# E-Book_Reader_Schematic.net
KiCad netlist of a schematic drawn in EAGLE
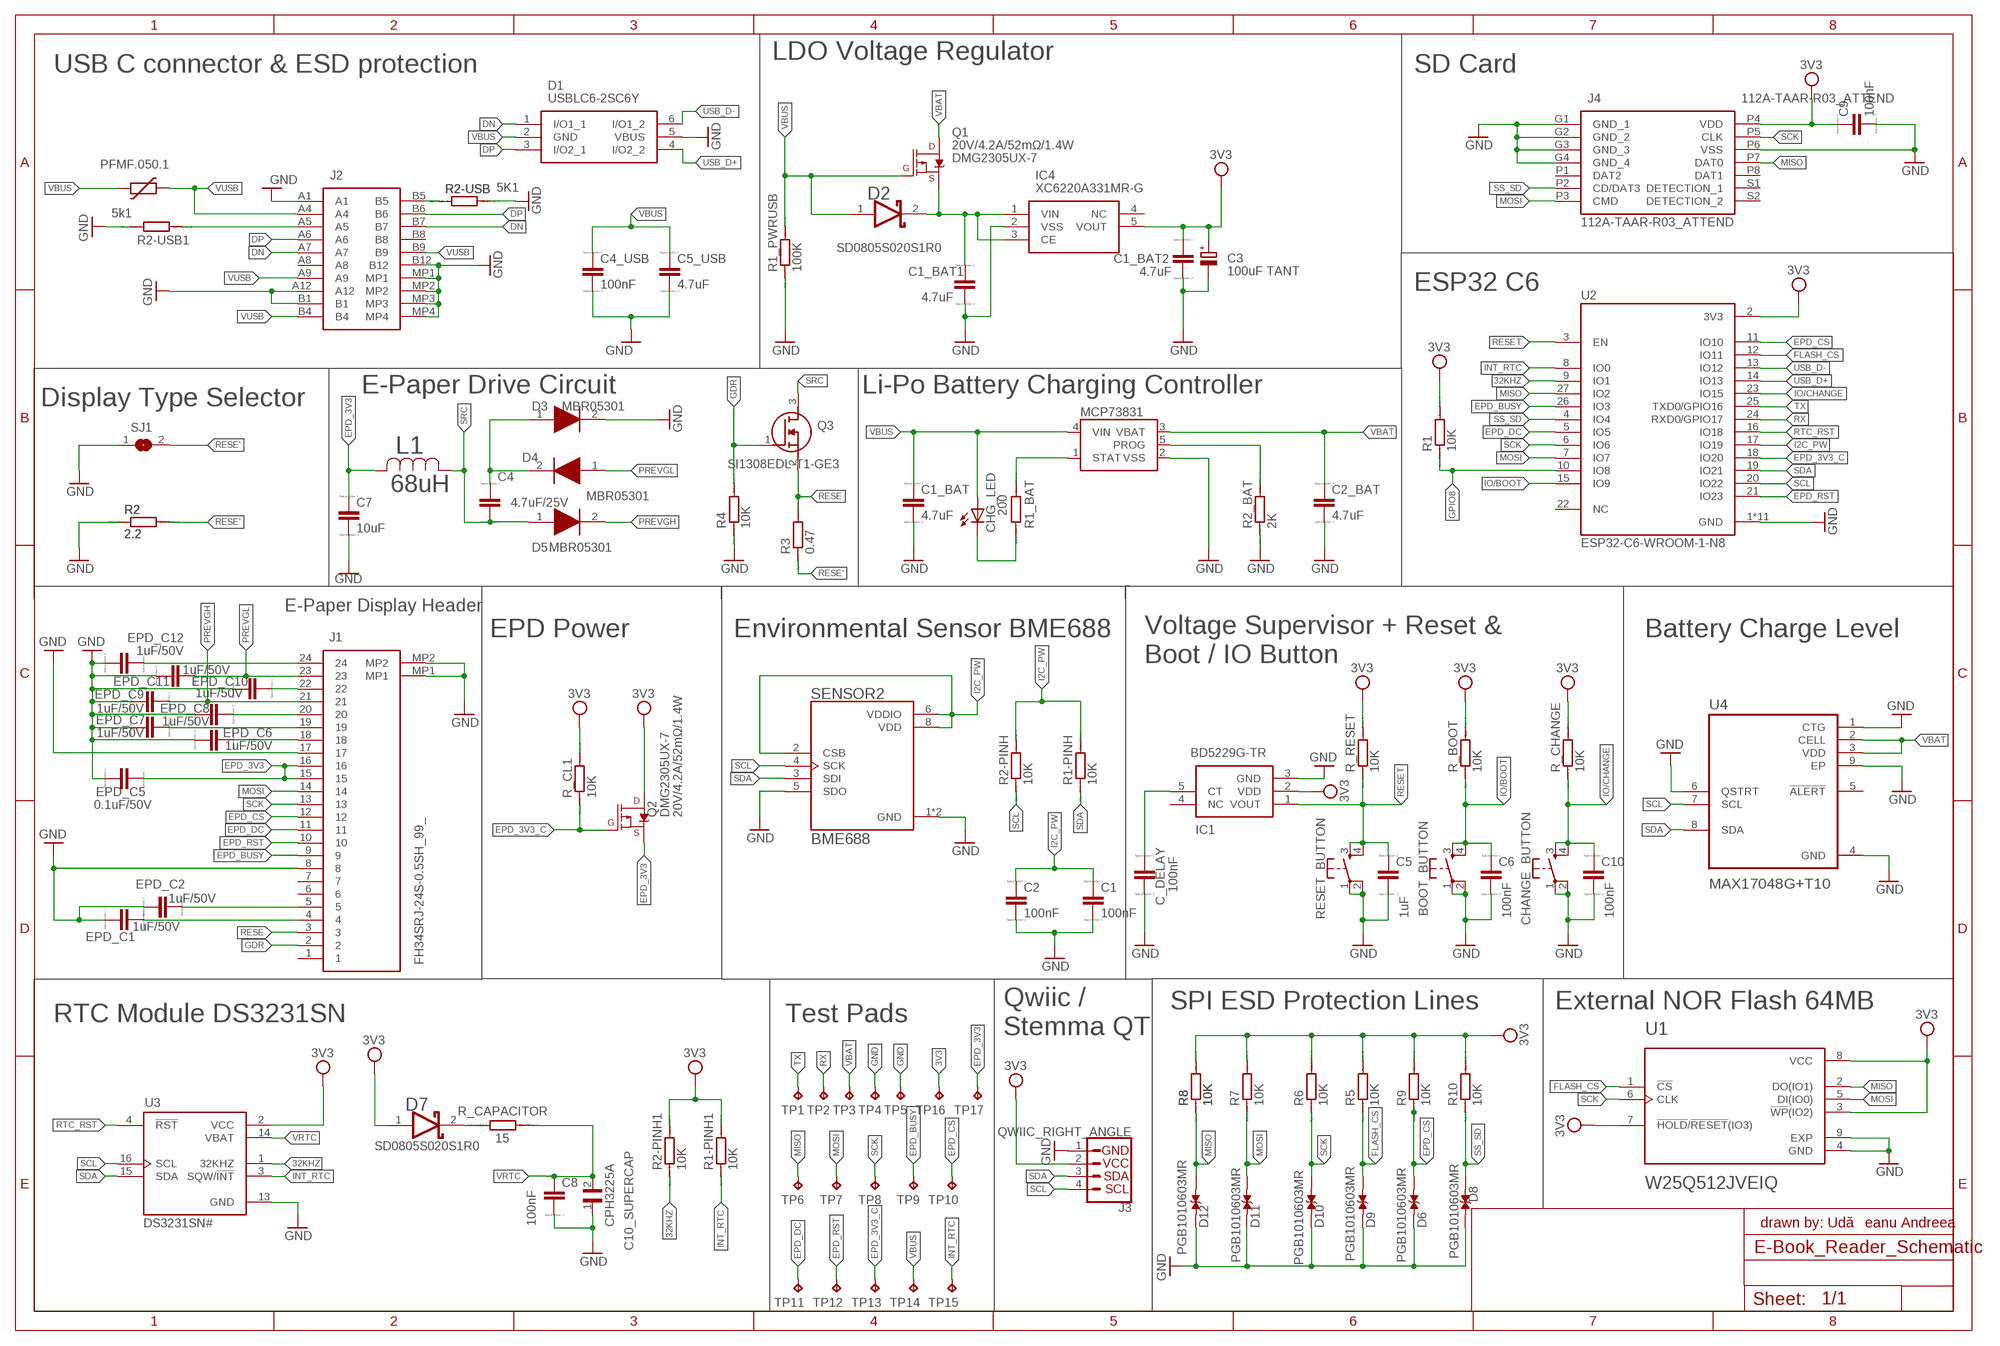
[diagram p0: schematic, sheet 1]

(export (version "E")
  (design (tool "Eeschema 10.0.6"))
  (components
    (comp (ref "BOOT_BUTTON")
      (value "BUTTON_CUSYOMV1")
      (footprint "eagle-import:MYBUTTON")
      (libsource (lib "eagle-import") (part "BUTTON_CUSYOMV1"))
    )
    (comp (ref "C1")
      (value "100nF")
      (footprint "eagle-import:EAGLE-LTSPICE_C0402")
      (libsource (lib "eagle-import") (part "EAGLE-LTSPICE_CC0402"))
    )
    (comp (ref "C1_BAT")
      (value "4.7uF")
      (footprint "eagle-import:EAGLE-LTSPICE_C0402")
      (libsource (lib "eagle-import") (part "EAGLE-LTSPICE_CC0402"))
    )
    (comp (ref "C1_BAT1")
      (value "4.7uF")
      (footprint "eagle-import:EAGLE-LTSPICE_C0402")
      (libsource (lib "eagle-import") (part "EAGLE-LTSPICE_CC0402"))
    )
    (comp (ref "C1_BAT2")
      (value "4.7uF")
      (footprint "eagle-import:EAGLE-LTSPICE_C0402")
      (libsource (lib "eagle-import") (part "EAGLE-LTSPICE_CC0402"))
    )
    (comp (ref "C2")
      (value "100nF")
      (footprint "eagle-import:EAGLE-LTSPICE_C0402")
      (libsource (lib "eagle-import") (part "EAGLE-LTSPICE_CC0402"))
    )
    (comp (ref "C2_BAT")
      (value "4.7uF")
      (footprint "eagle-import:EAGLE-LTSPICE_C0402")
      (libsource (lib "eagle-import") (part "EAGLE-LTSPICE_CC0402"))
    )
    (comp (ref "C3")
      (value "100uF TANT")
      (footprint "eagle-import:RCL_CT3528")
      (libsource (lib "eagle-import") (part "RCL_CPOL-EUCT3528"))
    )
    (comp (ref "C4")
      (value "4.7uF/25V")
      (footprint "eagle-import:EAGLE-LTSPICE_C0402")
      (libsource (lib "eagle-import") (part "EAGLE-LTSPICE_CC0402"))
    )
    (comp (ref "C4_USB")
      (value "100nF")
      (footprint "eagle-import:ESP32_WROVER_EAGLE-LTSPICE_C0402")
      (libsource (lib "eagle-import") (part "ESP32_WROVER_EAGLE-LTSPICE_CC0402"))
    )
    (comp (ref "C5")
      (value "1uF")
      (footprint "eagle-import:EAGLE-LTSPICE_C0402")
      (libsource (lib "eagle-import") (part "EAGLE-LTSPICE_CC0402"))
    )
    (comp (ref "C5_USB")
      (value "4.7uF")
      (footprint "eagle-import:ESP32_WROVER_EAGLE-LTSPICE_C0402")
      (libsource (lib "eagle-import") (part "ESP32_WROVER_EAGLE-LTSPICE_CC0402"))
    )
    (comp (ref "C6")
      (value "100nF")
      (footprint "eagle-import:EAGLE-LTSPICE_C0402")
      (libsource (lib "eagle-import") (part "EAGLE-LTSPICE_CC0402"))
    )
    (comp (ref "C7")
      (value "10uF")
      (footprint "eagle-import:EAGLE-LTSPICE_C0402")
      (libsource (lib "eagle-import") (part "EAGLE-LTSPICE_CC0402"))
    )
    (comp (ref "C8")
      (value "100nF")
      (footprint "eagle-import:EAGLE-LTSPICE_C0402")
      (libsource (lib "eagle-import") (part "EAGLE-LTSPICE_CC0402"))
    )
    (comp (ref "C9")
      (value "100nF")
      (footprint "eagle-import:ESP32_WROVER_EAGLE-LTSPICE_C0402")
      (libsource (lib "eagle-import") (part "ESP32_WROVER_EAGLE-LTSPICE_CC0402"))
    )
    (comp (ref "C10")
      (value "100nF")
      (footprint "eagle-import:EAGLE-LTSPICE_C0402")
      (libsource (lib "eagle-import") (part "EAGLE-LTSPICE_CC0402"))
    )
    (comp (ref "C10_SUPERCAP")
      (value "CPH3225A")
      (footprint "eagle-import:CAPCP3225X100N")
      (fields (field (name "MF") "Seiko Instruments"))
      (libsource (lib "eagle-import") (part "CPH3225A"))
    )
    (comp (ref "CHANGE_BUTTON")
      (value "BUTTON_CUSYOMV1")
      (footprint "eagle-import:MYBUTTON")
      (libsource (lib "eagle-import") (part "BUTTON_CUSYOMV1"))
    )
    (comp (ref "CHG_LED")
      (value "ADAFRUIT_LEDCHIP-LED0603")
      (footprint "eagle-import:ADAFRUIT_CHIP-LED0603")
      (libsource (lib "eagle-import") (part "ADAFRUIT_LEDCHIP-LED0603"))
    )
    (comp (ref "C_DELAY")
      (value "100nF")
      (footprint "eagle-import:EAGLE-LTSPICE_C0402")
      (libsource (lib "eagle-import") (part "EAGLE-LTSPICE_CC0402"))
    )
    (comp (ref "D1")
      (value "USBLC6-2SC6Y")
      (footprint "eagle-import:SOT95P280X145-6N")
      (fields (field (name "MF") "STMicroelectronics"))
      (libsource (lib "eagle-import") (part "USBLC6-2SC6Y"))
    )
    (comp (ref "D2")
      (value "SD0805S020S1R0")
      (footprint "eagle-import:ESP32_WROVER_AVX---SD0805S020S1R0_AVX_SD0805S020S1R0_0")
      (libsource (lib "eagle-import") (part "ESP32_WROVER_AVX---SD0805S020S1R0_AVX_SD0805S020S1R0_0_0"))
    )
    (comp (ref "D3")
      (value "MBR05301")
      (footprint "eagle-import:SOD3716X135N")
      (libsource (lib "eagle-import") (part "MBR05301"))
    )
    (comp (ref "D4")
      (value "MBR05301")
      (footprint "eagle-import:SOD3716X135N")
      (libsource (lib "eagle-import") (part "MBR05301"))
    )
    (comp (ref "D5")
      (value "MBR05301")
      (footprint "eagle-import:SOD3716X135N")
      (libsource (lib "eagle-import") (part "MBR05301"))
    )
    (comp (ref "D6")
      (value "PGB1010603MR")
      (footprint "eagle-import:DIOC1608X36N")
      (fields (field (name "MF") "Littelfuse Inc."))
      (libsource (lib "eagle-import") (part "PGB1010603MR"))
    )
    (comp (ref "D7")
      (value "SD0805S020S1R0")
      (footprint "eagle-import:ESP32_WROVER_AVX---SD0805S020S1R0_AVX_SD0805S020S1R0_0")
      (libsource (lib "eagle-import") (part "ESP32_WROVER_AVX---SD0805S020S1R0_AVX_SD0805S020S1R0_0_0"))
    )
    (comp (ref "D8")
      (value "PGB1010603MR")
      (footprint "eagle-import:DIOC1608X36N")
      (fields (field (name "MF") "Littelfuse Inc."))
      (libsource (lib "eagle-import") (part "PGB1010603MR"))
    )
    (comp (ref "D9")
      (value "PGB1010603MR")
      (footprint "eagle-import:DIOC1608X36N")
      (fields (field (name "MF") "Littelfuse Inc."))
      (libsource (lib "eagle-import") (part "PGB1010603MR"))
    )
    (comp (ref "D10")
      (value "PGB1010603MR")
      (footprint "eagle-import:DIOC1608X36N")
      (fields (field (name "MF") "Littelfuse Inc."))
      (libsource (lib "eagle-import") (part "PGB1010603MR"))
    )
    (comp (ref "D11")
      (value "PGB1010603MR")
      (footprint "eagle-import:DIOC1608X36N")
      (fields (field (name "MF") "Littelfuse Inc."))
      (libsource (lib "eagle-import") (part "PGB1010603MR"))
    )
    (comp (ref "D12")
      (value "PGB1010603MR")
      (footprint "eagle-import:DIOC1608X36N")
      (fields (field (name "MF") "Littelfuse Inc."))
      (libsource (lib "eagle-import") (part "PGB1010603MR"))
    )
    (comp (ref "EPD_C1")
      (value "1uF/50V")
      (footprint "eagle-import:EAGLE-LTSPICE_C0402")
      (libsource (lib "eagle-import") (part "EAGLE-LTSPICE_CC0402"))
    )
    (comp (ref "EPD_C2")
      (value "1uF/50V")
      (footprint "eagle-import:EAGLE-LTSPICE_C0402")
      (libsource (lib "eagle-import") (part "EAGLE-LTSPICE_CC0402"))
    )
    (comp (ref "EPD_C5")
      (value "0.1uF/50V")
      (footprint "eagle-import:EAGLE-LTSPICE_C0402")
      (libsource (lib "eagle-import") (part "EAGLE-LTSPICE_CC0402"))
    )
    (comp (ref "EPD_C6")
      (value "1uF/50V")
      (footprint "eagle-import:EAGLE-LTSPICE_C0402")
      (libsource (lib "eagle-import") (part "EAGLE-LTSPICE_CC0402"))
    )
    (comp (ref "EPD_C7")
      (value "1uF/50V")
      (footprint "eagle-import:EAGLE-LTSPICE_C0402")
      (libsource (lib "eagle-import") (part "EAGLE-LTSPICE_CC0402"))
    )
    (comp (ref "EPD_C8")
      (value "1uF/50V")
      (footprint "eagle-import:EAGLE-LTSPICE_C0402")
      (libsource (lib "eagle-import") (part "EAGLE-LTSPICE_CC0402"))
    )
    (comp (ref "EPD_C9")
      (value "1uF/50V")
      (footprint "eagle-import:EAGLE-LTSPICE_C0402")
      (libsource (lib "eagle-import") (part "EAGLE-LTSPICE_CC0402"))
    )
    (comp (ref "EPD_C10")
      (value "1uF/50V")
      (footprint "eagle-import:EAGLE-LTSPICE_C0402")
      (libsource (lib "eagle-import") (part "EAGLE-LTSPICE_CC0402"))
    )
    (comp (ref "EPD_C11")
      (value "1uF/50V")
      (footprint "eagle-import:EAGLE-LTSPICE_C0402")
      (libsource (lib "eagle-import") (part "EAGLE-LTSPICE_CC0402"))
    )
    (comp (ref "EPD_C12")
      (value "1uF/50V")
      (footprint "eagle-import:EAGLE-LTSPICE_C0402")
      (libsource (lib "eagle-import") (part "EAGLE-LTSPICE_CC0402"))
    )
    (comp (ref "IC1")
      (value "BD5229G-TR")
      (footprint "eagle-import:SOT95P280X125-5N")
      (fields (field (name "MOUSER_PART_NUMBER") "755-BD5229G-TR"))
      (libsource (lib "eagle-import") (part "BD5229G-TR"))
    )
    (comp (ref "IC4")
      (value "XC6220A331MR-G")
      (footprint "eagle-import:SOT95P280X120-5N")
      (fields (field (name "MOUSER_PART_NUMBER") "865-XC6220A331MR-G"))
      (libsource (lib "eagle-import") (part "XC6220A331MR-G"))
    )
    (comp (ref "J1")
      (value "FH34SRJ-24S-0.5SH_99_")
      (footprint "eagle-import:FH34SRJ24S05SH99")
      (fields
        (field (name "MANUFACTURER_PART_NUMBER") "FH34SRJ-24S-0.5SH(99)")
        (field (name "MOUSER_PART_NUMBER") "798-FH34SRJ24S05SH99")
      )
      (libsource (lib "eagle-import") (part "FH34SRJ-24S-0.5SH_99_"))
    )
    (comp (ref "J2")
      (value "SAMACSYS_PARTS_USB4110-GF-A")
      (footprint "eagle-import:SAMACSYS_PARTS_USB4110GFA")
      (fields
        (field (name "MANUFACTURER_PART_NUMBER") "USB4110-GF-A")
        (field (name "MOUSER_PART_NUMBER") "640-USB4110-GF-A")
      )
      (libsource (lib "eagle-import") (part "SAMACSYS_PARTS_USB4110-GF-A"))
    )
    (comp (ref "J3")
      (value "QWIIC_RIGHT_ANGLE")
      (footprint "eagle-import:JST04_1MM_RA")
      (libsource (lib "eagle-import") (part "QWIIC_CONNECTORJS-1MM"))
    )
    (comp (ref "J4")
      (value "112A-TAAR-R03_ATTEND")
      (footprint "eagle-import:112ATAARR03ATTEND")
      (fields (field (name "MANUFACTURER_PART_NUMBER") "112A-TAAR-R03 ATTEND"))
      (libsource (lib "eagle-import") (part "112A-TAAR-R03_ATTEND"))
    )
    (comp (ref "L1")
      (value "68uH")
      (footprint "eagle-import:IND_4828-WE-TPC_WRE")
      (fields
        (field (name "MANUFACTURER_PART_NUMBER") "744043680")
        (field (name "COPYRIGHT") "Copyright (C) 2024 Ultra Librarian. All rights reserved.")
      )
      (libsource (lib "eagle-import") (part "744043680IND_4828-WE-TPC_WRE"))
    )
    (comp (ref "MCP73831")
      (value "ESP32_WROVER_SPARKFUN-IC-POWER_MCP73831")
      (footprint "eagle-import:ESP32_WROVER_SPARKFUN-IC-POWER_SOT23-5")
      (libsource (lib "eagle-import") (part "ESP32_WROVER_SPARKFUN-IC-POWER_MCP73831"))
    )
    (comp (ref "PFMF.050.1")
      (value "ESP32C6_VARISTORCN1812")
      (footprint "eagle-import:ESP32C6_VARISTOR_CT_CN1812")
      (libsource (lib "eagle-import") (part "ESP32C6_VARISTORCN1812"))
    )
    (comp (ref "Q1")
      (value "20V/4.2A/52mΩ/1.4W")
      (footprint "eagle-import:ESP32_WROVER_SPARKFUN-DISCRETESEMI_SOT23-3")
      (libsource (lib "eagle-import") (part "ESP32_WROVER_SPARKFUN-DISCRETESEMI_MOSFET_PCH-DMG2305UX-7"))
    )
    (comp (ref "Q2")
      (value "20V/4.2A/52mΩ/1.4W")
      (footprint "eagle-import:ESP32_WROVER_SPARKFUN-DISCRETESEMI_SOT23-3")
      (libsource (lib "eagle-import") (part "ESP32_WROVER_SPARKFUN-DISCRETESEMI_MOSFET_PCH-DMG2305UX-7"))
    )
    (comp (ref "Q3")
      (value "SI1308EDL-T1-GE3")
      (footprint "eagle-import:SOT65P210X110-3N")
      (fields (field (name "MF") "Vishay Siliconix"))
      (libsource (lib "eagle-import") (part "SI1308EDL-T1-GE3"))
    )
    (comp (ref "R1")
      (value "10K")
      (footprint "eagle-import:ESP32_WROVER_EAGLE-LTSPICE_R0402")
      (libsource (lib "eagle-import") (part "ESP32_WROVER_EAGLE-LTSPICE_RR0402"))
    )
    (comp (ref "R1-PINH")
      (value "10K")
      (footprint "eagle-import:ESP32_WROVER_EAGLE-LTSPICE_R0402")
      (libsource (lib "eagle-import") (part "ESP32_WROVER_EAGLE-LTSPICE_RR0402"))
    )
    (comp (ref "R1-PINH1")
      (value "10K")
      (footprint "eagle-import:ESP32_WROVER_EAGLE-LTSPICE_R0402")
      (libsource (lib "eagle-import") (part "ESP32_WROVER_EAGLE-LTSPICE_RR0402"))
    )
    (comp (ref "R1_BAT")
      (value "200")
      (footprint "eagle-import:ESP32_WROVER_EAGLE-LTSPICE_R0402")
      (libsource (lib "eagle-import") (part "ESP32_WROVER_EAGLE-LTSPICE_RR0402"))
    )
    (comp (ref "R1_PWRUSB")
      (value "100K")
      (footprint "eagle-import:ESP32_WROVER_EAGLE-LTSPICE_R0402")
      (libsource (lib "eagle-import") (part "ESP32_WROVER_EAGLE-LTSPICE_RR0402"))
    )
    (comp (ref "R2")
      (value "2.2")
      (footprint "eagle-import:ESP32_WROVER_EAGLE-LTSPICE_R0402")
      (libsource (lib "eagle-import") (part "ESP32_WROVER_EAGLE-LTSPICE_RR0402"))
    )
    (comp (ref "R2-PINH")
      (value "10K")
      (footprint "eagle-import:ESP32_WROVER_EAGLE-LTSPICE_R0402")
      (libsource (lib "eagle-import") (part "ESP32_WROVER_EAGLE-LTSPICE_RR0402"))
    )
    (comp (ref "R2-PINH1")
      (value "10K")
      (footprint "eagle-import:ESP32_WROVER_EAGLE-LTSPICE_R0402")
      (libsource (lib "eagle-import") (part "ESP32_WROVER_EAGLE-LTSPICE_RR0402"))
    )
    (comp (ref "R2-USB")
      (value "5K1")
      (footprint "eagle-import:ESP32_WROVER_EAGLE-LTSPICE_R0402")
      (libsource (lib "eagle-import") (part "ESP32_WROVER_EAGLE-LTSPICE_RR0402"))
    )
    (comp (ref "R2-USB1")
      (value "5k1")
      (footprint "eagle-import:ESP32_WROVER_EAGLE-LTSPICE_R0402")
      (libsource (lib "eagle-import") (part "ESP32_WROVER_EAGLE-LTSPICE_RR0402"))
    )
    (comp (ref "R2_BAT")
      (value "2K")
      (footprint "eagle-import:ESP32_WROVER_EAGLE-LTSPICE_R0402")
      (libsource (lib "eagle-import") (part "ESP32_WROVER_EAGLE-LTSPICE_RR0402"))
    )
    (comp (ref "R3")
      (value "0.47")
      (footprint "eagle-import:ESP32_WROVER_EAGLE-LTSPICE_R0402")
      (libsource (lib "eagle-import") (part "ESP32_WROVER_EAGLE-LTSPICE_RR0402"))
    )
    (comp (ref "R4")
      (value "10K")
      (footprint "eagle-import:ESP32_WROVER_EAGLE-LTSPICE_R0402")
      (libsource (lib "eagle-import") (part "ESP32_WROVER_EAGLE-LTSPICE_RR0402"))
    )
    (comp (ref "R5")
      (value "10K")
      (footprint "eagle-import:ESP32_WROVER_EAGLE-LTSPICE_R0402")
      (libsource (lib "eagle-import") (part "ESP32_WROVER_EAGLE-LTSPICE_RR0402"))
    )
    (comp (ref "R6")
      (value "10K")
      (footprint "eagle-import:ESP32_WROVER_EAGLE-LTSPICE_R0402")
      (libsource (lib "eagle-import") (part "ESP32_WROVER_EAGLE-LTSPICE_RR0402"))
    )
    (comp (ref "R7")
      (value "10K")
      (footprint "eagle-import:ESP32_WROVER_EAGLE-LTSPICE_R0402")
      (libsource (lib "eagle-import") (part "ESP32_WROVER_EAGLE-LTSPICE_RR0402"))
    )
    (comp (ref "R8")
      (value "10K")
      (footprint "eagle-import:ESP32_WROVER_EAGLE-LTSPICE_R0402")
      (libsource (lib "eagle-import") (part "ESP32_WROVER_EAGLE-LTSPICE_RR0402"))
    )
    (comp (ref "R9")
      (value "10K")
      (footprint "eagle-import:ESP32_WROVER_EAGLE-LTSPICE_R0402")
      (libsource (lib "eagle-import") (part "ESP32_WROVER_EAGLE-LTSPICE_RR0402"))
    )
    (comp (ref "R10")
      (value "10K")
      (footprint "eagle-import:ESP32_WROVER_EAGLE-LTSPICE_R0402")
      (libsource (lib "eagle-import") (part "ESP32_WROVER_EAGLE-LTSPICE_RR0402"))
    )
    (comp (ref "RESET_BUTTON")
      (value "BUTTON_CUSYOMV1")
      (footprint "eagle-import:MYBUTTON")
      (libsource (lib "eagle-import") (part "BUTTON_CUSYOMV1"))
    )
    (comp (ref "R_BOOT")
      (value "10K")
      (footprint "eagle-import:ESP32_WROVER_EAGLE-LTSPICE_R0402")
      (libsource (lib "eagle-import") (part "ESP32_WROVER_EAGLE-LTSPICE_RR0402"))
    )
    (comp (ref "R_CAPACITOR")
      (value "15")
      (footprint "eagle-import:ESP32_WROVER_EAGLE-LTSPICE_R0402")
      (libsource (lib "eagle-import") (part "ESP32_WROVER_EAGLE-LTSPICE_RR0402"))
    )
    (comp (ref "R_CHANGE")
      (value "10K")
      (footprint "eagle-import:ESP32_WROVER_EAGLE-LTSPICE_R0402")
      (libsource (lib "eagle-import") (part "ESP32_WROVER_EAGLE-LTSPICE_RR0402"))
    )
    (comp (ref "R_CL1")
      (value "10K")
      (footprint "eagle-import:ESP32_WROVER_EAGLE-LTSPICE_R0402")
      (libsource (lib "eagle-import") (part "ESP32_WROVER_EAGLE-LTSPICE_RR0402"))
    )
    (comp (ref "R_RESET")
      (value "10K")
      (footprint "eagle-import:ESP32_WROVER_EAGLE-LTSPICE_R0402")
      (libsource (lib "eagle-import") (part "ESP32_WROVER_EAGLE-LTSPICE_RR0402"))
    )
    (comp (ref "SENSOR2")
      (value "BME688")
      (footprint "eagle-import:ESP32_WROVER_BME680_PSON80P300X300X100-8N")
      (fields (field (name "MF") "Bosch Sensortec") (field (name "MP") "BME680"))
      (libsource (lib "eagle-import") (part "ESP32_WROVER_BME680_BME680"))
    )
    (comp (ref "SJ1") (value "SJ") (footprint "eagle-import:SJ") (libsource (lib "eagle-import") (part "SJ")))
    (comp (ref "TP1")
      (value "TPTP20R")
      (footprint "eagle-import:TP20R")
      (libsource (lib "eagle-import") (part "TP"))
    )
    (comp (ref "TP2")
      (value "TP")
      (footprint "eagle-import:TP20R")
      (libsource (lib "eagle-import") (part "TP"))
    )
    (comp (ref "TP3")
      (value "TP")
      (footprint "eagle-import:TP20R")
      (libsource (lib "eagle-import") (part "TP"))
    )
    (comp (ref "TP4")
      (value "TP")
      (footprint "eagle-import:TP20R")
      (libsource (lib "eagle-import") (part "TP"))
    )
    (comp (ref "TP5")
      (value "TP")
      (footprint "eagle-import:TP20R")
      (libsource (lib "eagle-import") (part "TP"))
    )
    (comp (ref "TP6")
      (value "TP")
      (footprint "eagle-import:TP20R")
      (libsource (lib "eagle-import") (part "TP"))
    )
    (comp (ref "TP7")
      (value "TP")
      (footprint "eagle-import:TP20R")
      (libsource (lib "eagle-import") (part "TP"))
    )
    (comp (ref "TP8")
      (value "TP")
      (footprint "eagle-import:TP20R")
      (libsource (lib "eagle-import") (part "TP"))
    )
    (comp (ref "TP9")
      (value "TP")
      (footprint "eagle-import:TP20R")
      (libsource (lib "eagle-import") (part "TP"))
    )
    (comp (ref "TP10")
      (value "TP")
      (footprint "eagle-import:TP20R")
      (libsource (lib "eagle-import") (part "TP"))
    )
    (comp (ref "TP11")
      (value "TP")
      (footprint "eagle-import:TP20R")
      (libsource (lib "eagle-import") (part "TP"))
    )
    (comp (ref "TP12")
      (value "TP")
      (footprint "eagle-import:TP20R")
      (libsource (lib "eagle-import") (part "TP"))
    )
    (comp (ref "TP13")
      (value "TP")
      (footprint "eagle-import:TP20R")
      (libsource (lib "eagle-import") (part "TP"))
    )
    (comp (ref "TP14")
      (value "TP")
      (footprint "eagle-import:TP20R")
      (libsource (lib "eagle-import") (part "TP"))
    )
    (comp (ref "TP15")
      (value "TP")
      (footprint "eagle-import:TP20R")
      (libsource (lib "eagle-import") (part "TP"))
    )
    (comp (ref "TP16")
      (value "TP")
      (footprint "eagle-import:TP20R")
      (libsource (lib "eagle-import") (part "TP"))
    )
    (comp (ref "TP17")
      (value "TP")
      (footprint "eagle-import:TP20R")
      (libsource (lib "eagle-import") (part "TP"))
    )
    (comp (ref "U1")
      (value "W25Q512JVEIQ")
      (footprint "eagle-import:SON127P600X800X80-9N")
      (fields (field (name "MF") "Winbond Electronics"))
      (libsource (lib "eagle-import") (part "W25Q512JVEIQ"))
    )
    (comp (ref "U2")
      (value "ESP32-C6-WROOM-1-N8")
      (footprint "eagle-import:XCVR_ESP32-C6-WROOM-1-N8")
      (fields (field (name "MF") "Espressif Systems"))
      (libsource (lib "eagle-import") (part "ESP32-C6-WROOM-1-N8"))
    )
    (comp (ref "U3")
      (value "DS3231SN#")
      (footprint "eagle-import:SOIC127P1032X265-16N")
      (fields (field (name "MF") "Analog Devices"))
      (libsource (lib "eagle-import") (part "DS3231SN#"))
    )
    (comp (ref "U4")
      (value "MAX17048G+T10")
      (footprint "eagle-import:SON50P200X200X80-9N")
      (fields (field (name "MF") "Analog Devices"))
      (libsource (lib "eagle-import") (part "MAX17048G+T10"))
    )
  )
  (nets
    (net (code "1") (name "3V3") (class "Default")
      (node (ref "C1_BAT2") (pin "1") (pinfunction "1_1") (pintype "passive"))
      (node (ref "C3") (pin "+") (pinfunction "+_+") (pintype "passive"))
      (node (ref "C9") (pin "1") (pinfunction "1_1") (pintype "passive"))
      (node (ref "D7") (pin "1") (pinfunction "ANODE_1") (pintype "bidirectional"))
      (node (ref "IC1") (pin "2") (pinfunction "VDD_2") (pintype "bidirectional"))
      (node (ref "IC4") (pin "5") (pinfunction "VOUT_5") (pintype "bidirectional"))
      (node (ref "J3") (pin "2") (pinfunction "2_2") (pintype "power_in"))
      (node (ref "J4") (pin "P4") (pinfunction "VDD_P4") (pintype "bidirectional"))
      (node (ref "Q2") (pin "3") (pinfunction "D_3") (pintype "bidirectional"))
      (node (ref "R1") (pin "2") (pinfunction "2_2") (pintype "passive"))
      (node (ref "R1-PINH1") (pin "2") (pinfunction "2_2") (pintype "passive"))
      (node (ref "R10") (pin "2") (pinfunction "2_2") (pintype "passive"))
      (node (ref "R2-PINH1") (pin "2") (pinfunction "2_2") (pintype "passive"))
      (node (ref "R5") (pin "2") (pinfunction "2_2") (pintype "passive"))
      (node (ref "R6") (pin "2") (pinfunction "2_2") (pintype "passive"))
      (node (ref "R7") (pin "2") (pinfunction "2_2") (pintype "passive"))
      (node (ref "R8") (pin "2") (pinfunction "2_2") (pintype "passive"))
      (node (ref "R9") (pin "2") (pinfunction "2_2") (pintype "passive"))
      (node (ref "R_BOOT") (pin "2") (pinfunction "2_2") (pintype "passive"))
      (node (ref "R_CHANGE") (pin "2") (pinfunction "2_2") (pintype "passive"))
      (node (ref "R_CL1") (pin "2") (pinfunction "2_2") (pintype "passive"))
      (node (ref "R_RESET") (pin "2") (pinfunction "2_2") (pintype "passive"))
      (node (ref "TP16") (pin "TP") (pinfunction "TP_TP") (pintype "input"))
      (node (ref "U1") (pin "3") (pinfunction "~{WP}(IO2)_3") (pintype "bidirectional"))
      (node (ref "U1") (pin "7") (pinfunction "~{HOLD}/~{RESET}(IO3)_7") (pintype "bidirectional"))
      (node (ref "U1") (pin "8") (pinfunction "VCC_8") (pintype "power_in"))
      (node (ref "U2") (pin "2") (pinfunction "3V3_2") (pintype "power_in"))
      (node (ref "U3") (pin "2") (pinfunction "VCC_2") (pintype "power_in"))
    )
    (net (code "2") (name "32KHZ") (class "Default")
      (node (ref "R2-PINH1") (pin "1") (pinfunction "1_1") (pintype "passive"))
      (node (ref "U2") (pin "9") (pinfunction "IO1_9") (pintype "bidirectional"))
      (node (ref "U3") (pin "1") (pinfunction "32KHZ_1") (pintype "output"))
    )
    (net (code "3") (name "DN") (class "Default")
      (node (ref "D1") (pin "1") (pinfunction "I/O1_1_1") (pintype "bidirectional"))
      (node (ref "J2") (pin "A7") (pinfunction "A7_A7") (pintype "bidirectional"))
      (node (ref "J2") (pin "B7") (pinfunction "B7_B7") (pintype "bidirectional"))
    )
    (net (code "4") (name "DP") (class "Default")
      (node (ref "D1") (pin "3") (pinfunction "I/O2_1_3") (pintype "bidirectional"))
      (node (ref "J2") (pin "A6") (pinfunction "A6_A6") (pintype "bidirectional"))
      (node (ref "J2") (pin "B6") (pinfunction "B6_B6") (pintype "bidirectional"))
    )
    (net (code "5") (name "EPD_3V3") (class "Default")
      (node (ref "C7") (pin "1") (pinfunction "1_1") (pintype "passive"))
      (node (ref "EPD_C5") (pin "1") (pinfunction "1_1") (pintype "passive"))
      (node (ref "J1") (pin "15") (pinfunction "15_15") (pintype "bidirectional"))
      (node (ref "J1") (pin "16") (pinfunction "16_16") (pintype "bidirectional"))
      (node (ref "L1") (pin "2") (pinfunction "2_2") (pintype "passive"))
      (node (ref "Q2") (pin "2") (pinfunction "S_2") (pintype "bidirectional"))
      (node (ref "TP17") (pin "TP") (pinfunction "TP_TP") (pintype "input"))
    )
    (net (code "6") (name "EPD_3V3_C") (class "Default")
      (node (ref "Q2") (pin "1") (pinfunction "G_1") (pintype "bidirectional"))
      (node (ref "R_CL1") (pin "1") (pinfunction "1_1") (pintype "passive"))
      (node (ref "TP13") (pin "TP") (pinfunction "TP_TP") (pintype "input"))
      (node (ref "U2") (pin "18") (pinfunction "IO20_18") (pintype "bidirectional"))
    )
    (net (code "7") (name "EPD_BUSY") (class "Default")
      (node (ref "J1") (pin "9") (pinfunction "9_9") (pintype "bidirectional"))
      (node (ref "TP9") (pin "TP") (pinfunction "TP_TP") (pintype "input"))
      (node (ref "U2") (pin "26") (pinfunction "IO3_26") (pintype "bidirectional"))
    )
    (net (code "8") (name "EPD_CS") (class "Default")
      (node (ref "D6") (pin "2") (pinfunction "2_2") (pintype "passive"))
      (node (ref "J1") (pin "12") (pinfunction "12_12") (pintype "bidirectional"))
      (node (ref "R9") (pin "1") (pinfunction "1_1") (pintype "passive"))
      (node (ref "TP10") (pin "TP") (pinfunction "TP_TP") (pintype "input"))
      (node (ref "U2") (pin "11") (pinfunction "IO10_11") (pintype "bidirectional"))
    )
    (net (code "9") (name "EPD_DC") (class "Default")
      (node (ref "J1") (pin "11") (pinfunction "11_11") (pintype "bidirectional"))
      (node (ref "TP11") (pin "TP") (pinfunction "TP_TP") (pintype "input"))
      (node (ref "U2") (pin "5") (pinfunction "IO5_5") (pintype "bidirectional"))
    )
    (net (code "10") (name "EPD_RST") (class "Default")
      (node (ref "J1") (pin "10") (pinfunction "10_10") (pintype "bidirectional"))
      (node (ref "TP12") (pin "TP") (pinfunction "TP_TP") (pintype "input"))
      (node (ref "U2") (pin "21") (pinfunction "IO23_21") (pintype "bidirectional"))
    )
    (net (code "11") (name "FLASH_CS") (class "Default")
      (node (ref "D9") (pin "2") (pinfunction "2_2") (pintype "passive"))
      (node (ref "R5") (pin "1") (pinfunction "1_1") (pintype "passive"))
      (node (ref "U1") (pin "1") (pinfunction "~{CS}_1") (pintype "input"))
      (node (ref "U2") (pin "12") (pinfunction "IO11_12") (pintype "bidirectional"))
    )
    (net (code "12") (name "GDR") (class "Default")
      (node (ref "J1") (pin "2") (pinfunction "2_2") (pintype "bidirectional"))
      (node (ref "Q3") (pin "1") (pinfunction "G_1") (pintype "bidirectional"))
      (node (ref "R4") (pin "2") (pinfunction "2_2") (pintype "passive"))
    )
    (net (code "13") (name "GND") (class "Default")
      (node (ref "BOOT_BUTTON") (pin "1") (pinfunction "1_1") (pintype "passive"))
      (node (ref "BOOT_BUTTON") (pin "2") (pinfunction "2_2") (pintype "passive"))
      (node (ref "C1") (pin "2") (pinfunction "2_2") (pintype "passive"))
      (node (ref "C10") (pin "2") (pinfunction "2_2") (pintype "passive"))
      (node (ref "C10_SUPERCAP") (pin "1") (pinfunction "1_1") (pintype "passive"))
      (node (ref "C1_BAT") (pin "2") (pinfunction "2_2") (pintype "passive"))
      (node (ref "C1_BAT1") (pin "2") (pinfunction "2_2") (pintype "passive"))
      (node (ref "C1_BAT2") (pin "2") (pinfunction "2_2") (pintype "passive"))
      (node (ref "C2") (pin "2") (pinfunction "2_2") (pintype "passive"))
      (node (ref "C2_BAT") (pin "2") (pinfunction "2_2") (pintype "passive"))
      (node (ref "C3") (pin "-") (pinfunction "-_-") (pintype "passive"))
      (node (ref "C4_USB") (pin "2") (pinfunction "2_2") (pintype "passive"))
      (node (ref "C5") (pin "2") (pinfunction "2_2") (pintype "passive"))
      (node (ref "C5_USB") (pin "2") (pinfunction "2_2") (pintype "passive"))
      (node (ref "C6") (pin "2") (pinfunction "2_2") (pintype "passive"))
      (node (ref "C7") (pin "2") (pinfunction "2_2") (pintype "passive"))
      (node (ref "C8") (pin "2") (pinfunction "2_2") (pintype "passive"))
      (node (ref "C9") (pin "2") (pinfunction "2_2") (pintype "passive"))
      (node (ref "CHANGE_BUTTON") (pin "1") (pinfunction "1_1") (pintype "passive"))
      (node (ref "CHANGE_BUTTON") (pin "2") (pinfunction "2_2") (pintype "passive"))
      (node (ref "C_DELAY") (pin "2") (pinfunction "2_2") (pintype "passive"))
      (node (ref "D1") (pin "5") (pinfunction "VBUS_5") (pintype "bidirectional"))
      (node (ref "D10") (pin "1") (pinfunction "1_1") (pintype "passive"))
      (node (ref "D11") (pin "1") (pinfunction "1_1") (pintype "passive"))
      (node (ref "D12") (pin "1") (pinfunction "1_1") (pintype "passive"))
      (node (ref "D3") (pin "2") (pinfunction "K_2") (pintype "bidirectional"))
      (node (ref "D6") (pin "1") (pinfunction "1_1") (pintype "passive"))
      (node (ref "D8") (pin "1") (pinfunction "1_1") (pintype "passive"))
      (node (ref "D9") (pin "1") (pinfunction "1_1") (pintype "passive"))
      (node (ref "EPD_C1") (pin "2") (pinfunction "2_2") (pintype "passive"))
      (node (ref "EPD_C10") (pin "2") (pinfunction "2_2") (pintype "passive"))
      (node (ref "EPD_C11") (pin "2") (pinfunction "2_2") (pintype "passive"))
      (node (ref "EPD_C12") (pin "2") (pinfunction "2_2") (pintype "passive"))
      (node (ref "EPD_C2") (pin "2") (pinfunction "2_2") (pintype "passive"))
      (node (ref "EPD_C5") (pin "2") (pinfunction "2_2") (pintype "passive"))
      (node (ref "EPD_C6") (pin "2") (pinfunction "2_2") (pintype "passive"))
      (node (ref "EPD_C7") (pin "2") (pinfunction "2_2") (pintype "passive"))
      (node (ref "EPD_C8") (pin "2") (pinfunction "2_2") (pintype "passive"))
      (node (ref "EPD_C9") (pin "2") (pinfunction "2_2") (pintype "passive"))
      (node (ref "IC1") (pin "3") (pinfunction "GND_3") (pintype "bidirectional"))
      (node (ref "IC4") (pin "2") (pinfunction "VSS_2") (pintype "bidirectional"))
      (node (ref "J1") (pin "17") (pinfunction "17_17") (pintype "bidirectional"))
      (node (ref "J1") (pin "8") (pinfunction "8_8") (pintype "bidirectional"))
      (node (ref "J1") (pin "MP1") (pinfunction "MP1_MP1") (pintype "bidirectional"))
      (node (ref "J1") (pin "MP2") (pinfunction "MP2_MP2") (pintype "bidirectional"))
      (node (ref "J2") (pin "A1") (pinfunction "A1_A1") (pintype "bidirectional"))
      (node (ref "J2") (pin "A12") (pinfunction "A12_A12") (pintype "bidirectional"))
      (node (ref "J2") (pin "B1") (pinfunction "B1_B1") (pintype "bidirectional"))
      (node (ref "J2") (pin "B12") (pinfunction "B12_B12") (pintype "bidirectional"))
      (node (ref "J2") (pin "MP1") (pinfunction "MP1_MP1") (pintype "bidirectional"))
      (node (ref "J2") (pin "MP2") (pinfunction "MP2_MP2") (pintype "bidirectional"))
      (node (ref "J2") (pin "MP3") (pinfunction "MP3_MP3") (pintype "bidirectional"))
      (node (ref "J2") (pin "MP4") (pinfunction "MP4_MP4") (pintype "bidirectional"))
      (node (ref "J3") (pin "1") (pinfunction "1_1") (pintype "power_in"))
      (node (ref "J4") (pin "G1") (pinfunction "GND_1_G1") (pintype "bidirectional"))
      (node (ref "J4") (pin "G2") (pinfunction "GND_2_G2") (pintype "bidirectional"))
      (node (ref "J4") (pin "G3") (pinfunction "GND_3_G3") (pintype "bidirectional"))
      (node (ref "J4") (pin "G4") (pinfunction "GND_4_G4") (pintype "bidirectional"))
      (node (ref "J4") (pin "P6") (pinfunction "VSS_P6") (pintype "bidirectional"))
      (node (ref "MCP73831") (pin "2") (pinfunction "VSS_2") (pintype "power_in"))
      (node (ref "R1_PWRUSB") (pin "1") (pinfunction "1_1") (pintype "passive"))
      (node (ref "R2") (pin "1") (pinfunction "1_1") (pintype "passive"))
      (node (ref "R2-USB") (pin "2") (pinfunction "2_2") (pintype "passive"))
      (node (ref "R2-USB1") (pin "1") (pinfunction "1_1") (pintype "passive"))
      (node (ref "R2_BAT") (pin "1") (pinfunction "1_1") (pintype "passive"))
      (node (ref "R4") (pin "1") (pinfunction "1_1") (pintype "passive"))
      (node (ref "RESET_BUTTON") (pin "1") (pinfunction "1_1") (pintype "passive"))
      (node (ref "RESET_BUTTON") (pin "2") (pinfunction "2_2") (pintype "passive"))
      (node (ref "SENSOR2") (pin "1") (pinfunction "GND_1") (pintype "power_in"))
      (node (ref "SENSOR2") (pin "5") (pinfunction "SDO_5") (pintype "bidirectional"))
      (node (ref "SENSOR2") (pin "7") (pinfunction "GND_7") (pintype "power_in"))
      (node (ref "SJ1") (pin "1") (pinfunction "1_1") (pintype "passive"))
      (node (ref "TP4") (pin "TP") (pinfunction "TP_TP") (pintype "input"))
      (node (ref "TP5") (pin "TP") (pinfunction "TP_TP") (pintype "input"))
      (node (ref "U1") (pin "4") (pinfunction "GND_4") (pintype "power_in"))
      (node (ref "U1") (pin "9") (pinfunction "EXP_9") (pintype "passive"))
      (node (ref "U2") (pin "1") (pinfunction "GND_1") (pintype "power_in"))
      (node (ref "U2") (pin "28") (pinfunction "GND_28") (pintype "power_in"))
      (node (ref "U2") (pin "29_1") (pinfunction "GND_29_1") (pintype "power_in"))
      (node (ref "U2") (pin "29_2") (pinfunction "GND_29_2") (pintype "power_in"))
      (node (ref "U2") (pin "29_3") (pinfunction "GND_29_3") (pintype "power_in"))
      (node (ref "U2") (pin "29_4") (pinfunction "GND_29_4") (pintype "power_in"))
      (node (ref "U2") (pin "29_5") (pinfunction "GND_29_5") (pintype "power_in"))
      (node (ref "U2") (pin "29_6") (pinfunction "GND_29_6") (pintype "power_in"))
      (node (ref "U2") (pin "29_7") (pinfunction "GND_29_7") (pintype "power_in"))
      (node (ref "U2") (pin "29_8") (pinfunction "GND_29_8") (pintype "power_in"))
      (node (ref "U2") (pin "29_9") (pinfunction "GND_29_9") (pintype "power_in"))
      (node (ref "U3") (pin "13") (pinfunction "GND_13") (pintype "power_in"))
      (node (ref "U4") (pin "1") (pinfunction "CTG_1") (pintype "power_in"))
      (node (ref "U4") (pin "4") (pinfunction "GND_4") (pintype "power_in"))
      (node (ref "U4") (pin "6") (pinfunction "QSTRT_6") (pintype "input"))
      (node (ref "U4") (pin "9") (pinfunction "EP_9") (pintype "power_in"))
    )
    (net (code "14") (name "GPIO8") (class "Default")
      (node (ref "R1") (pin "1") (pinfunction "1_1") (pintype "passive"))
      (node (ref "U2") (pin "10") (pinfunction "IO8_10") (pintype "bidirectional"))
    )
    (net (code "15") (name "I2C_PW") (class "Default")
      (node (ref "C1") (pin "1") (pinfunction "1_1") (pintype "passive"))
      (node (ref "C2") (pin "1") (pinfunction "1_1") (pintype "passive"))
      (node (ref "R1-PINH") (pin "2") (pinfunction "2_2") (pintype "passive"))
      (node (ref "R2-PINH") (pin "2") (pinfunction "2_2") (pintype "passive"))
      (node (ref "SENSOR2") (pin "2") (pinfunction "CSB_2") (pintype "input"))
      (node (ref "SENSOR2") (pin "6") (pinfunction "VDDIO_6") (pintype "power_in"))
      (node (ref "SENSOR2") (pin "8") (pinfunction "VDD_8") (pintype "power_in"))
      (node (ref "U2") (pin "17") (pinfunction "IO19_17") (pintype "bidirectional"))
    )
    (net (code "16") (name "INT_RTC") (class "Default")
      (node (ref "R1-PINH1") (pin "1") (pinfunction "1_1") (pintype "passive"))
      (node (ref "TP15") (pin "TP") (pinfunction "TP_TP") (pintype "input"))
      (node (ref "U2") (pin "8") (pinfunction "IO0_8") (pintype "bidirectional"))
      (node (ref "U3") (pin "3") (pinfunction "SQW/~{INT}_3") (pintype "output"))
    )
    (net (code "17") (name "IO{slash}BOOT") (class "Default")
      (node (ref "BOOT_BUTTON") (pin "3") (pinfunction "3_3") (pintype "passive"))
      (node (ref "BOOT_BUTTON") (pin "4") (pinfunction "4_4") (pintype "passive"))
      (node (ref "C6") (pin "1") (pinfunction "1_1") (pintype "passive"))
      (node (ref "R_BOOT") (pin "1") (pinfunction "1_1") (pintype "passive"))
      (node (ref "U2") (pin "15") (pinfunction "IO9_15") (pintype "bidirectional"))
    )
    (net (code "18") (name "IO{slash}CHANGE") (class "Default")
      (node (ref "C10") (pin "1") (pinfunction "1_1") (pintype "passive"))
      (node (ref "CHANGE_BUTTON") (pin "3") (pinfunction "3_3") (pintype "passive"))
      (node (ref "CHANGE_BUTTON") (pin "4") (pinfunction "4_4") (pintype "passive"))
      (node (ref "R_CHANGE") (pin "1") (pinfunction "1_1") (pintype "passive"))
      (node (ref "U2") (pin "23") (pinfunction "IO15_23") (pintype "bidirectional"))
    )
    (net (code "19") (name "MISO") (class "Default")
      (node (ref "D12") (pin "2") (pinfunction "2_2") (pintype "passive"))
      (node (ref "J4") (pin "P7") (pinfunction "DAT0_P7") (pintype "bidirectional"))
      (node (ref "R8") (pin "1") (pinfunction "1_1") (pintype "passive"))
      (node (ref "TP6") (pin "TP") (pinfunction "TP_TP") (pintype "input"))
      (node (ref "U1") (pin "2") (pinfunction "DO(IO1)_2") (pintype "bidirectional"))
      (node (ref "U2") (pin "27") (pinfunction "IO2_27") (pintype "bidirectional"))
    )
    (net (code "20") (name "MOSI") (class "Default")
      (node (ref "D11") (pin "2") (pinfunction "2_2") (pintype "passive"))
      (node (ref "J1") (pin "14") (pinfunction "14_14") (pintype "bidirectional"))
      (node (ref "J4") (pin "P3") (pinfunction "CMD_P3") (pintype "bidirectional"))
      (node (ref "R7") (pin "1") (pinfunction "1_1") (pintype "passive"))
      (node (ref "TP7") (pin "TP") (pinfunction "TP_TP") (pintype "input"))
      (node (ref "U1") (pin "5") (pinfunction "DI(IO0)_5") (pintype "bidirectional"))
      (node (ref "U2") (pin "7") (pinfunction "IO7_7") (pintype "bidirectional"))
    )
    (net (code "21") (name "Net-(CHG_LED-PadC)") (class "Default")
      (node (ref "CHG_LED") (pin "C") (pinfunction "C_C") (pintype "passive"))
      (node (ref "R1_BAT") (pin "1") (pinfunction "1_1") (pintype "passive"))
    )
    (net (code "22") (name "Net-(D2-CATHODE)") (class "Default")
      (node (ref "C1_BAT1") (pin "1") (pinfunction "1_1") (pintype "passive"))
      (node (ref "D2") (pin "2") (pinfunction "CATHODE_2") (pintype "bidirectional"))
      (node (ref "IC4") (pin "1") (pinfunction "VIN_1") (pintype "bidirectional"))
      (node (ref "IC4") (pin "3") (pinfunction "CE_3") (pintype "bidirectional"))
      (node (ref "Q1") (pin "2") (pinfunction "S_2") (pintype "bidirectional"))
    )
    (net (code "23") (name "Net-(D3-A)") (class "Default")
      (node (ref "C4") (pin "1") (pinfunction "1_1") (pintype "passive"))
      (node (ref "D3") (pin "1") (pinfunction "A_1") (pintype "bidirectional"))
      (node (ref "D4") (pin "2") (pinfunction "K_2") (pintype "bidirectional"))
    )
    (net (code "24") (name "Net-(D7-CATHODE)") (class "Default")
      (node (ref "D7") (pin "2") (pinfunction "CATHODE_2") (pintype "bidirectional"))
      (node (ref "R_CAPACITOR") (pin "2") (pinfunction "2_2") (pintype "passive"))
    )
    (net (code "25") (name "Net-(EPD_C1-Pad1)") (class "Default")
      (node (ref "EPD_C1") (pin "1") (pinfunction "1_1") (pintype "passive"))
      (node (ref "J1") (pin "4") (pinfunction "4_4") (pintype "bidirectional"))
    )
    (net (code "26") (name "Net-(EPD_C2-Pad1)") (class "Default")
      (node (ref "EPD_C2") (pin "1") (pinfunction "1_1") (pintype "passive"))
      (node (ref "J1") (pin "5") (pinfunction "5_5") (pintype "bidirectional"))
    )
    (net (code "27") (name "Net-(EPD_C6-Pad1)") (class "Default")
      (node (ref "EPD_C6") (pin "1") (pinfunction "1_1") (pintype "passive"))
      (node (ref "J1") (pin "18") (pinfunction "18_18") (pintype "bidirectional"))
    )
    (net (code "28") (name "Net-(EPD_C7-Pad1)") (class "Default")
      (node (ref "EPD_C7") (pin "1") (pinfunction "1_1") (pintype "passive"))
      (node (ref "J1") (pin "19") (pinfunction "19_19") (pintype "bidirectional"))
    )
    (net (code "29") (name "Net-(EPD_C8-Pad1)") (class "Default")
      (node (ref "EPD_C8") (pin "1") (pinfunction "1_1") (pintype "passive"))
      (node (ref "J1") (pin "20") (pinfunction "20_20") (pintype "bidirectional"))
    )
    (net (code "30") (name "Net-(EPD_C10-Pad1)") (class "Default")
      (node (ref "EPD_C10") (pin "1") (pinfunction "1_1") (pintype "passive"))
      (node (ref "J1") (pin "22") (pinfunction "22_22") (pintype "bidirectional"))
    )
    (net (code "31") (name "Net-(EPD_C12-Pad1)") (class "Default")
      (node (ref "EPD_C12") (pin "1") (pinfunction "1_1") (pintype "passive"))
      (node (ref "J1") (pin "24") (pinfunction "24_24") (pintype "bidirectional"))
    )
    (net (code "32") (name "Net-(IC1-CT)") (class "Default")
      (node (ref "C_DELAY") (pin "1") (pinfunction "1_1") (pintype "passive"))
      (node (ref "IC1") (pin "5") (pinfunction "CT_5") (pintype "bidirectional"))
    )
    (net (code "33") (name "Net-(J2-PadA5)") (class "Default")
      (node (ref "J2") (pin "A5") (pinfunction "A5_A5") (pintype "bidirectional"))
      (node (ref "R2-USB1") (pin "2") (pinfunction "2_2") (pintype "passive"))
    )
    (net (code "34") (name "Net-(J2-PadB5)") (class "Default")
      (node (ref "J2") (pin "B5") (pinfunction "B5_B5") (pintype "bidirectional"))
      (node (ref "R2-USB") (pin "1") (pinfunction "1_1") (pintype "passive"))
    )
    (net (code "35") (name "Net-(MCP73831-PROG)") (class "Default")
      (node (ref "MCP73831") (pin "5") (pinfunction "PROG_5") (pintype "input"))
      (node (ref "R2_BAT") (pin "2") (pinfunction "2_2") (pintype "passive"))
    )
    (net (code "36") (name "Net-(MCP73831-STAT)") (class "Default")
      (node (ref "MCP73831") (pin "1") (pinfunction "STAT_1") (pintype "output"))
      (node (ref "R1_BAT") (pin "2") (pinfunction "2_2") (pintype "passive"))
    )
    (net (code "37") (name "PREVGH") (class "Default")
      (node (ref "D5") (pin "2") (pinfunction "K_2") (pintype "bidirectional"))
      (node (ref "EPD_C9") (pin "1") (pinfunction "1_1") (pintype "passive"))
      (node (ref "J1") (pin "21") (pinfunction "21_21") (pintype "bidirectional"))
    )
    (net (code "38") (name "PREVGL") (class "Default")
      (node (ref "D4") (pin "1") (pinfunction "A_1") (pintype "bidirectional"))
      (node (ref "EPD_C11") (pin "1") (pinfunction "1_1") (pintype "passive"))
      (node (ref "J1") (pin "23") (pinfunction "23_23") (pintype "bidirectional"))
    )
    (net (code "39") (name "RESE") (class "Default")
      (node (ref "J1") (pin "3") (pinfunction "3_3") (pintype "bidirectional"))
      (node (ref "Q3") (pin "2") (pinfunction "S_2") (pintype "bidirectional"))
      (node (ref "R3") (pin "2") (pinfunction "2_2") (pintype "passive"))
    )
    (net (code "40") (name "RESE'") (class "Default")
      (node (ref "R2") (pin "2") (pinfunction "2_2") (pintype "passive"))
      (node (ref "R3") (pin "1") (pinfunction "1_1") (pintype "passive"))
      (node (ref "SJ1") (pin "2") (pinfunction "2_2") (pintype "passive"))
    )
    (net (code "41") (name "RESET") (class "Default")
      (node (ref "C5") (pin "1") (pinfunction "1_1") (pintype "passive"))
      (node (ref "IC1") (pin "1") (pinfunction "VOUT_1") (pintype "bidirectional"))
      (node (ref "RESET_BUTTON") (pin "3") (pinfunction "3_3") (pintype "passive"))
      (node (ref "RESET_BUTTON") (pin "4") (pinfunction "4_4") (pintype "passive"))
      (node (ref "R_RESET") (pin "1") (pinfunction "1_1") (pintype "passive"))
      (node (ref "U2") (pin "3") (pinfunction "EN_3") (pintype "input"))
    )
    (net (code "42") (name "RTC_RST") (class "Default")
      (node (ref "U2") (pin "16") (pinfunction "IO18_16") (pintype "bidirectional"))
      (node (ref "U3") (pin "4") (pinfunction "~{RST}_4") (pintype "input"))
    )
    (net (code "43") (name "RX") (class "Default")
      (node (ref "TP2") (pin "TP") (pinfunction "TP_TP") (pintype "input"))
      (node (ref "U2") (pin "24") (pinfunction "RXD0/GPIO17_24") (pintype "bidirectional"))
    )
    (net (code "44") (name "SCK") (class "Default")
      (node (ref "D10") (pin "2") (pinfunction "2_2") (pintype "passive"))
      (node (ref "J1") (pin "13") (pinfunction "13_13") (pintype "bidirectional"))
      (node (ref "J4") (pin "P5") (pinfunction "CLK_P5") (pintype "bidirectional"))
      (node (ref "R6") (pin "1") (pinfunction "1_1") (pintype "passive"))
      (node (ref "TP8") (pin "TP") (pinfunction "TP_TP") (pintype "input"))
      (node (ref "U1") (pin "6") (pinfunction "CLK_6") (pintype "input"))
      (node (ref "U2") (pin "6") (pinfunction "IO6_6") (pintype "bidirectional"))
    )
    (net (code "45") (name "SCL") (class "Default")
      (node (ref "J3") (pin "4") (pinfunction "4_4") (pintype "passive"))
      (node (ref "R2-PINH") (pin "1") (pinfunction "1_1") (pintype "passive"))
      (node (ref "SENSOR2") (pin "4") (pinfunction "SCK_4") (pintype "input"))
      (node (ref "U2") (pin "20") (pinfunction "IO22_20") (pintype "bidirectional"))
      (node (ref "U3") (pin "16") (pinfunction "SCL_16") (pintype "input"))
      (node (ref "U4") (pin "7") (pinfunction "SCL_7") (pintype "input"))
    )
    (net (code "46") (name "SDA") (class "Default")
      (node (ref "J3") (pin "3") (pinfunction "3_3") (pintype "passive"))
      (node (ref "R1-PINH") (pin "1") (pinfunction "1_1") (pintype "passive"))
      (node (ref "SENSOR2") (pin "3") (pinfunction "SDI_3") (pintype "bidirectional"))
      (node (ref "U2") (pin "19") (pinfunction "IO21_19") (pintype "bidirectional"))
      (node (ref "U3") (pin "15") (pinfunction "SDA_15") (pintype "bidirectional"))
      (node (ref "U4") (pin "8") (pinfunction "SDA_8") (pintype "bidirectional"))
    )
    (net (code "47") (name "SRC") (class "Default")
      (node (ref "C4") (pin "2") (pinfunction "2_2") (pintype "passive"))
      (node (ref "D5") (pin "1") (pinfunction "A_1") (pintype "bidirectional"))
      (node (ref "L1") (pin "1") (pinfunction "1_1") (pintype "passive"))
      (node (ref "Q3") (pin "3") (pinfunction "D_3") (pintype "bidirectional"))
    )
    (net (code "48") (name "SS_SD") (class "Default")
      (node (ref "D8") (pin "2") (pinfunction "2_2") (pintype "passive"))
      (node (ref "J4") (pin "P2") (pinfunction "CD/DAT3_P2") (pintype "bidirectional"))
      (node (ref "R10") (pin "1") (pinfunction "1_1") (pintype "passive"))
      (node (ref "U2") (pin "4") (pinfunction "IO4_4") (pintype "bidirectional"))
    )
    (net (code "49") (name "TX") (class "Default")
      (node (ref "TP1") (pin "TP") (pinfunction "TP_TP") (pintype "input"))
      (node (ref "U2") (pin "25") (pinfunction "TXD0/GPIO16_25") (pintype "bidirectional"))
    )
    (net (code "50") (name "USB_D+") (class "Default")
      (node (ref "D1") (pin "4") (pinfunction "I/O2_2_4") (pintype "bidirectional"))
      (node (ref "U2") (pin "14") (pinfunction "IO13_14") (pintype "bidirectional"))
    )
    (net (code "51") (name "USB_D-") (class "Default")
      (node (ref "D1") (pin "6") (pinfunction "I/O1_2_6") (pintype "bidirectional"))
      (node (ref "U2") (pin "13") (pinfunction "IO12_13") (pintype "bidirectional"))
    )
    (net (code "52") (name "VBAT") (class "Default")
      (node (ref "C2_BAT") (pin "1") (pinfunction "1_1") (pintype "passive"))
      (node (ref "MCP73831") (pin "3") (pinfunction "VBAT_3") (pintype "power_in"))
      (node (ref "Q1") (pin "3") (pinfunction "D_3") (pintype "bidirectional"))
      (node (ref "TP3") (pin "TP") (pinfunction "TP_TP") (pintype "input"))
      (node (ref "U4") (pin "2") (pinfunction "CELL_2") (pintype "power_in"))
      (node (ref "U4") (pin "3") (pinfunction "VDD_3") (pintype "power_in"))
    )
    (net (code "53") (name "VBUS") (class "Default")
      (node (ref "C1_BAT") (pin "1") (pinfunction "1_1") (pintype "passive"))
      (node (ref "C4_USB") (pin "1") (pinfunction "1_1") (pintype "passive"))
      (node (ref "C5_USB") (pin "1") (pinfunction "1_1") (pintype "passive"))
      (node (ref "CHG_LED") (pin "A") (pinfunction "A_A") (pintype "passive"))
      (node (ref "D1") (pin "2") (pinfunction "GND_2") (pintype "bidirectional"))
      (node (ref "D2") (pin "1") (pinfunction "ANODE_1") (pintype "bidirectional"))
      (node (ref "MCP73831") (pin "4") (pinfunction "VIN_4") (pintype "power_in"))
      (node (ref "PFMF.050.1") (pin "1") (pinfunction "1_1") (pintype "passive"))
      (node (ref "Q1") (pin "1") (pinfunction "G_1") (pintype "bidirectional"))
      (node (ref "R1_PWRUSB") (pin "2") (pinfunction "2_2") (pintype "passive"))
      (node (ref "TP14") (pin "TP") (pinfunction "TP_TP") (pintype "input"))
    )
    (net (code "54") (name "VRTC") (class "Default")
      (node (ref "C10_SUPERCAP") (pin "2") (pinfunction "2_2") (pintype "passive"))
      (node (ref "C8") (pin "1") (pinfunction "1_1") (pintype "passive"))
      (node (ref "R_CAPACITOR") (pin "1") (pinfunction "1_1") (pintype "passive"))
      (node (ref "U3") (pin "14") (pinfunction "VBAT_14") (pintype "power_in"))
    )
    (net (code "55") (name "VUSB") (class "Default")
      (node (ref "J2") (pin "A4") (pinfunction "A4_A4") (pintype "bidirectional"))
      (node (ref "J2") (pin "A9") (pinfunction "A9_A9") (pintype "bidirectional"))
      (node (ref "J2") (pin "B4") (pinfunction "B4_B4") (pintype "bidirectional"))
      (node (ref "J2") (pin "B9") (pinfunction "B9_B9") (pintype "bidirectional"))
      (node (ref "PFMF.050.1") (pin "2") (pinfunction "2_2") (pintype "passive"))
    )
    (net (code "56") (name "unconnected-(IC1-NC-Pad4)") (class "Default")
      (node (ref "IC1") (pin "4") (pinfunction "NC_4") (pintype "no_connect"))
    )
    (net (code "57") (name "unconnected-(IC4-NC-Pad4)") (class "Default")
      (node (ref "IC4") (pin "4") (pinfunction "NC_4") (pintype "no_connect"))
    )
    (net (code "58") (name "unconnected-(J1-Pad1)") (class "Default")
      (node (ref "J1") (pin "1") (pinfunction "1_1") (pintype "bidirectional"))
    )
    (net (code "59") (name "unconnected-(J1-Pad6)") (class "Default")
      (node (ref "J1") (pin "6") (pinfunction "6_6") (pintype "bidirectional"))
    )
    (net (code "60") (name "unconnected-(J1-Pad7)") (class "Default")
      (node (ref "J1") (pin "7") (pinfunction "7_7") (pintype "bidirectional"))
    )
    (net (code "61") (name "unconnected-(J2-PadA8)") (class "Default")
      (node (ref "J2") (pin "A8") (pinfunction "A8_A8") (pintype "bidirectional"))
    )
    (net (code "62") (name "unconnected-(J2-PadB8)") (class "Default")
      (node (ref "J2") (pin "B8") (pinfunction "B8_B8") (pintype "bidirectional"))
    )
    (net (code "63") (name "unconnected-(J4-DAT1-PadP8)") (class "Default")
      (node (ref "J4") (pin "P8") (pinfunction "DAT1_P8") (pintype "bidirectional"))
    )
    (net (code "64") (name "unconnected-(J4-DAT2-PadP1)") (class "Default")
      (node (ref "J4") (pin "P1") (pinfunction "DAT2_P1") (pintype "bidirectional"))
    )
    (net (code "65") (name "unconnected-(J4-DETECTION_1-PadS1)") (class "Default")
      (node (ref "J4") (pin "S1") (pinfunction "DETECTION_1_S1") (pintype "bidirectional"))
    )
    (net (code "66") (name "unconnected-(J4-DETECTION_2-PadS2)") (class "Default")
      (node (ref "J4") (pin "S2") (pinfunction "DETECTION_2_S2") (pintype "bidirectional"))
    )
    (net (code "67") (name "unconnected-(U2-NC-Pad22)") (class "Default")
      (node (ref "U2") (pin "22") (pinfunction "NC_22") (pintype "no_connect"))
    )
    (net (code "68") (name "unconnected-(U4-~{ALERT}-Pad5)") (class "Default")
      (node (ref "U4") (pin "5") (pinfunction "~{ALERT}_5") (pintype "output"))
    )
  )
)
